# SNES-logo-base.net
KiCad netlist of a schematic drawn in EAGLE
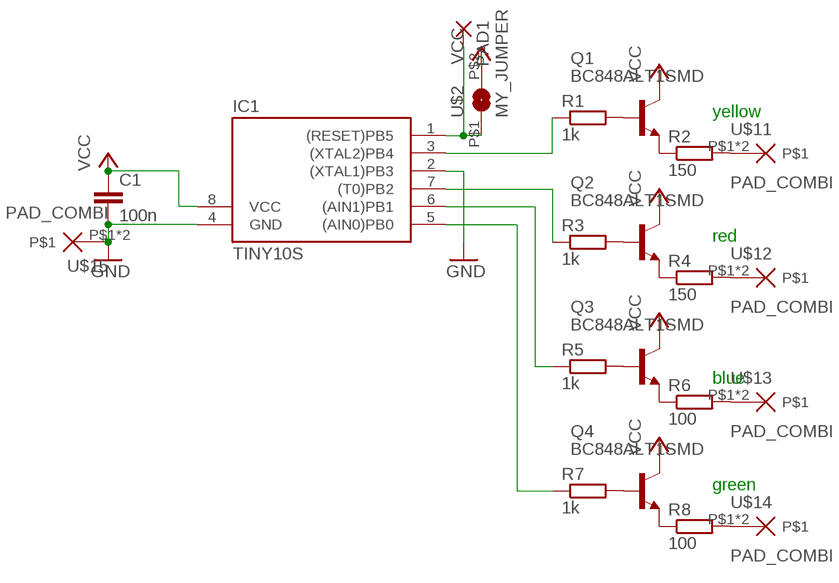
[diagram p0: schematic, sheet 1]

(export (version "E")
  (design (tool "Eeschema 10.0.6"))
  (components
    (comp (ref "C1")
      (value "100n")
      (footprint "eagle-import:Z0805")
      (libsource (lib "eagle-import") (part "C0805"))
    )
    (comp (ref "IC1")
      (value "TINY10S")
      (footprint "eagle-import:SOIC8")
      (libsource (lib "eagle-import") (part "TINY10S"))
    )
    (comp (ref "PAD1")
      (value "SMD2")
      (footprint "eagle-import:SMD1,27-2,54")
      (libsource (lib "eagle-import") (part "SMD2"))
    )
    (comp (ref "Q1")
      (value "BC848ALT1SMD")
      (footprint "eagle-import:SOT23")
      (libsource (lib "eagle-import") (part "BC848SMDALT1"))
    )
    (comp (ref "Q2")
      (value "BC848ALT1SMD")
      (footprint "eagle-import:SOT23")
      (libsource (lib "eagle-import") (part "BC848SMDALT1"))
    )
    (comp (ref "Q3")
      (value "BC848ALT1SMD")
      (footprint "eagle-import:SOT23")
      (libsource (lib "eagle-import") (part "BC848SMDALT1"))
    )
    (comp (ref "Q4")
      (value "BC848ALT1SMD")
      (footprint "eagle-import:SOT23")
      (libsource (lib "eagle-import") (part "BC848SMDALT1"))
    )
    (comp (ref "R1")
      (value "1k")
      (footprint "eagle-import:Z0805")
      (libsource (lib "eagle-import") (part "R0805"))
    )
    (comp (ref "R2")
      (value "150")
      (footprint "eagle-import:Z0805")
      (libsource (lib "eagle-import") (part "R0805"))
    )
    (comp (ref "R3")
      (value "1k")
      (footprint "eagle-import:Z0805")
      (libsource (lib "eagle-import") (part "R0805"))
    )
    (comp (ref "R4")
      (value "150")
      (footprint "eagle-import:Z0805")
      (libsource (lib "eagle-import") (part "R0805"))
    )
    (comp (ref "R5")
      (value "1k")
      (footprint "eagle-import:Z0805")
      (libsource (lib "eagle-import") (part "R0805"))
    )
    (comp (ref "R6")
      (value "100")
      (footprint "eagle-import:Z0805")
      (libsource (lib "eagle-import") (part "R0805"))
    )
    (comp (ref "R7")
      (value "1k")
      (footprint "eagle-import:Z0805")
      (libsource (lib "eagle-import") (part "R0805"))
    )
    (comp (ref "R8")
      (value "100")
      (footprint "eagle-import:Z0805")
      (libsource (lib "eagle-import") (part "R0805"))
    )
    (comp (ref "U$2")
      (value "MY_JUMPER")
      (footprint "eagle-import:MYJUMP")
      (libsource (lib "eagle-import") (part "MY_JUMPER"))
    )
    (comp (ref "U$11")
      (value "PAD_COMBI")
      (footprint "eagle-import:PAD_COMBI")
      (libsource (lib "eagle-import") (part "PAD_COMBI"))
    )
    (comp (ref "U$12")
      (value "PAD_COMBI")
      (footprint "eagle-import:PAD_COMBI")
      (libsource (lib "eagle-import") (part "PAD_COMBI"))
    )
    (comp (ref "U$13")
      (value "PAD_COMBI")
      (footprint "eagle-import:PAD_COMBI")
      (libsource (lib "eagle-import") (part "PAD_COMBI"))
    )
    (comp (ref "U$14")
      (value "PAD_COMBI")
      (footprint "eagle-import:PAD_COMBI")
      (libsource (lib "eagle-import") (part "PAD_COMBI"))
    )
    (comp (ref "U$15")
      (value "PAD_COMBI")
      (footprint "eagle-import:PAD_COMBI")
      (libsource (lib "eagle-import") (part "PAD_COMBI"))
    )
  )
  (nets
    (net (code "1") (name "GND") (class "Default")
      (node (ref "C1") (pin "2") (pinfunction "2_2") (pintype "passive"))
      (node (ref "IC1") (pin "2") (pinfunction "(XTAL1)PB3_2") (pintype "bidirectional"))
      (node (ref "IC1") (pin "4") (pinfunction "GND_4") (pintype "power_in"))
      (node (ref "U$15") (pin "P$1") (pinfunction "P$1_P$1") (pintype "bidirectional"))
      (node (ref "U$15") (pin "P$2") (pinfunction "P$1_P$2") (pintype "bidirectional"))
    )
    (net (code "2") (name "Net-(IC1-(AIN0)PB0)") (class "Default")
      (node (ref "IC1") (pin "5") (pinfunction "(AIN0)PB0_5") (pintype "bidirectional"))
      (node (ref "R7") (pin "1") (pinfunction "1_1") (pintype "passive"))
    )
    (net (code "3") (name "Net-(IC1-(AIN1)PB1)") (class "Default")
      (node (ref "IC1") (pin "6") (pinfunction "(AIN1)PB1_6") (pintype "bidirectional"))
      (node (ref "R5") (pin "1") (pinfunction "1_1") (pintype "passive"))
    )
    (net (code "4") (name "Net-(IC1-(RESET)PB5)") (class "Default")
      (node (ref "IC1") (pin "1") (pinfunction "(RESET)PB5_1") (pintype "bidirectional"))
      (node (ref "PAD1") (pin "1") (pinfunction "P_1") (pintype "passive"))
      (node (ref "U$2") (pin "P$1") (pinfunction "1_P$1") (pintype "passive"))
    )
    (net (code "5") (name "Net-(IC1-(T0)PB2)") (class "Default")
      (node (ref "IC1") (pin "7") (pinfunction "(T0)PB2_7") (pintype "bidirectional"))
      (node (ref "R3") (pin "1") (pinfunction "1_1") (pintype "passive"))
    )
    (net (code "6") (name "Net-(IC1-(XTAL2)PB4)") (class "Default")
      (node (ref "IC1") (pin "3") (pinfunction "(XTAL2)PB4_3") (pintype "bidirectional"))
      (node (ref "R1") (pin "1") (pinfunction "1_1") (pintype "passive"))
    )
    (net (code "7") (name "Net-(Q1-B)") (class "Default")
      (node (ref "Q1") (pin "1") (pinfunction "B_1") (pintype "passive"))
      (node (ref "R1") (pin "2") (pinfunction "2_2") (pintype "passive"))
    )
    (net (code "8") (name "Net-(Q1-E)") (class "Default")
      (node (ref "Q1") (pin "2") (pinfunction "E_2") (pintype "passive"))
      (node (ref "R2") (pin "1") (pinfunction "1_1") (pintype "passive"))
    )
    (net (code "9") (name "Net-(Q2-B)") (class "Default")
      (node (ref "Q2") (pin "1") (pinfunction "B_1") (pintype "passive"))
      (node (ref "R3") (pin "2") (pinfunction "2_2") (pintype "passive"))
    )
    (net (code "10") (name "Net-(Q2-E)") (class "Default")
      (node (ref "Q2") (pin "2") (pinfunction "E_2") (pintype "passive"))
      (node (ref "R4") (pin "1") (pinfunction "1_1") (pintype "passive"))
    )
    (net (code "11") (name "Net-(Q3-B)") (class "Default")
      (node (ref "Q3") (pin "1") (pinfunction "B_1") (pintype "passive"))
      (node (ref "R5") (pin "2") (pinfunction "2_2") (pintype "passive"))
    )
    (net (code "12") (name "Net-(Q3-E)") (class "Default")
      (node (ref "Q3") (pin "2") (pinfunction "E_2") (pintype "passive"))
      (node (ref "R6") (pin "1") (pinfunction "1_1") (pintype "passive"))
    )
    (net (code "13") (name "Net-(Q4-B)") (class "Default")
      (node (ref "Q4") (pin "1") (pinfunction "B_1") (pintype "passive"))
      (node (ref "R7") (pin "2") (pinfunction "2_2") (pintype "passive"))
    )
    (net (code "14") (name "Net-(Q4-E)") (class "Default")
      (node (ref "Q4") (pin "2") (pinfunction "E_2") (pintype "passive"))
      (node (ref "R8") (pin "1") (pinfunction "1_1") (pintype "passive"))
    )
    (net (code "15") (name "Net-(R2-Pad2)") (class "Default")
      (node (ref "R2") (pin "2") (pinfunction "2_2") (pintype "passive"))
      (node (ref "U$11") (pin "P$1") (pinfunction "P$1_P$1") (pintype "bidirectional"))
      (node (ref "U$11") (pin "P$2") (pinfunction "P$1_P$2") (pintype "bidirectional"))
    )
    (net (code "16") (name "Net-(R4-Pad2)") (class "Default")
      (node (ref "R4") (pin "2") (pinfunction "2_2") (pintype "passive"))
      (node (ref "U$12") (pin "P$1") (pinfunction "P$1_P$1") (pintype "bidirectional"))
      (node (ref "U$12") (pin "P$2") (pinfunction "P$1_P$2") (pintype "bidirectional"))
    )
    (net (code "17") (name "Net-(R6-Pad2)") (class "Default")
      (node (ref "R6") (pin "2") (pinfunction "2_2") (pintype "passive"))
      (node (ref "U$13") (pin "P$1") (pinfunction "P$1_P$1") (pintype "bidirectional"))
      (node (ref "U$13") (pin "P$2") (pinfunction "P$1_P$2") (pintype "bidirectional"))
    )
    (net (code "18") (name "Net-(R8-Pad2)") (class "Default")
      (node (ref "R8") (pin "2") (pinfunction "2_2") (pintype "passive"))
      (node (ref "U$14") (pin "P$1") (pinfunction "P$1_P$1") (pintype "bidirectional"))
      (node (ref "U$14") (pin "P$2") (pinfunction "P$1_P$2") (pintype "bidirectional"))
    )
    (net (code "19") (name "VCC") (class "Default")
      (node (ref "C1") (pin "1") (pinfunction "1_1") (pintype "passive"))
      (node (ref "IC1") (pin "8") (pinfunction "VCC_8") (pintype "power_in"))
      (node (ref "Q1") (pin "3") (pinfunction "C_3") (pintype "passive"))
      (node (ref "Q2") (pin "3") (pinfunction "C_3") (pintype "passive"))
      (node (ref "Q3") (pin "3") (pinfunction "C_3") (pintype "passive"))
      (node (ref "Q4") (pin "3") (pinfunction "C_3") (pintype "passive"))
      (node (ref "U$2") (pin "P$2") (pinfunction "2_P$2") (pintype "passive"))
    )
  )
)
